# DM1097_MODULE.net
KiCad netlist of a schematic drawn in Altium Designer
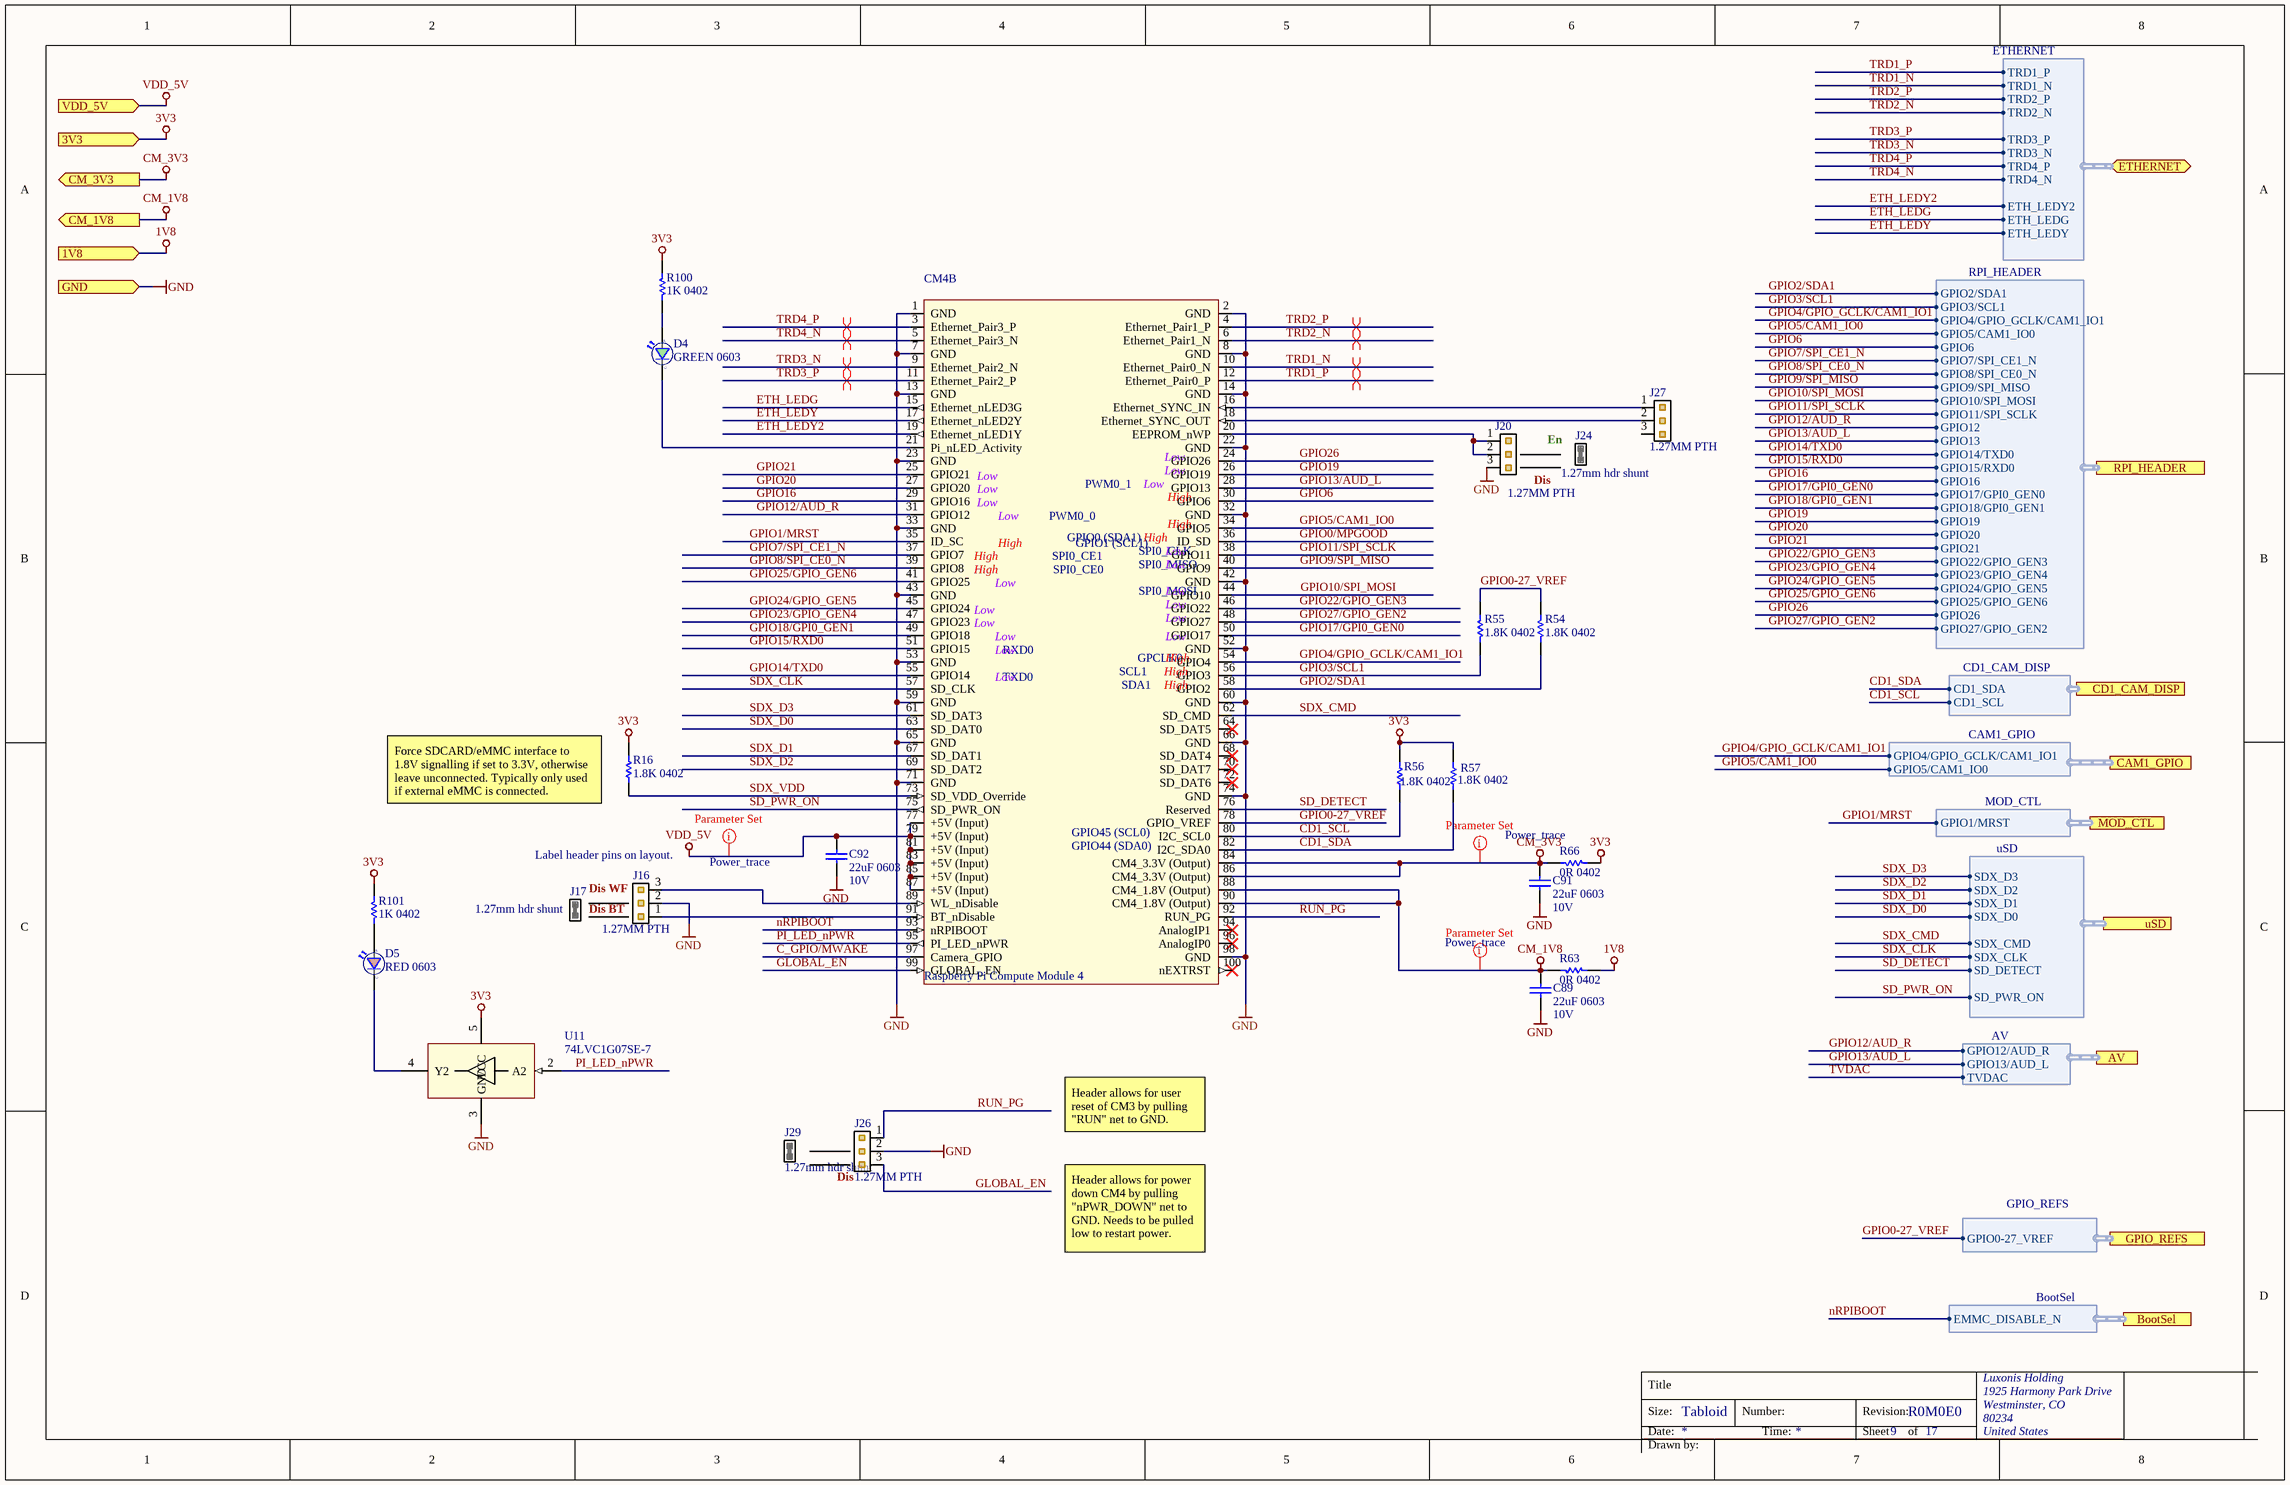
[diagram p0: DM1097_MODULE.SchDoc]

(export (version "E")
  (design (tool "Eeschema 10.0.6"))
  (components
    (comp (ref "C89")
      (value "22uF 0603")
      (footprint "CAP_Altium_Vault_Generic:CAPC0603(1608)100_N")
      (description "CAP CER 22UF 10V X5R 0603 20%")
      (fields (field (name "TOLERANCE") "20%") (field (name "VOLTAGE RATING") "10V"))
      (libsource (lib "LuxonisMaster") (part "GRM188R61A226ME15D"))
    )
    (comp (ref "C91")
      (value "22uF 0603")
      (footprint "CAP_Altium_Vault_Generic:CAPC0603(1608)100_N")
      (description "CAP CER 22UF 10V X5R 0603 20%")
      (fields (field (name "TOLERANCE") "20%") (field (name "VOLTAGE RATING") "10V"))
      (libsource (lib "LuxonisMaster") (part "GRM188R61A226ME15D"))
    )
    (comp (ref "C92")
      (value "22uF 0603")
      (footprint "CAP_Altium_Vault_Generic:CAPC0603(1608)100_N")
      (description "CAP CER 22UF 10V X5R 0603 20%")
      (fields (field (name "TOLERANCE") "20%") (field (name "VOLTAGE RATING") "10V"))
      (libsource (lib "LuxonisMaster") (part "GRM188R61A226ME15D"))
    )
    (comp (ref "CM4")
      (value "Raspberry Pi Compute Module 4")
      (footprint "CM4-DF40HC(3.0)-100DS-0.4v_3mm_1.5mm")
      (description "Raspberry Pi Compute Module 4\r\nTwo receptacle 100-pin connectors")
      (libsource (lib "DM1097_SchLib") (part "CM4"))
    )
    (comp (ref "D4")
      (value "GREEN 0603")
      (footprint "LuxonisMaster:SML_D1xx8W")
      (description "LED GREEN DIFFUSED 0603 SMD Green 572nm LED Indication - Discrete 2.2V 0603 (1608 Metric)")
      (fields (field (name "MANUFACTURER") "Rohm") (field (name "MANUFACTURER PART NUMBER") "SML-D12M8WT86"))
      (libsource (lib "LuxonisMaster") (part "SML-D12M8WT86"))
    )
    (comp (ref "D5")
      (value "RED 0603")
      (footprint "LuxonisMaster:SML_D1xx8W")
      (description "LED RED DIFFUSED 0603 SMD Red 620nm LED Indication - Discrete 2.2V 0603 (1608 Metric)")
      (libsource (lib "LuxonisMaster") (part "SML-D12U8WT86"))
    )
    (comp (ref "J16")
      (value "1.27MM PTH")
      (footprint "LuxonisMaster:GRPB031VWVN-RC")
      (description "CONN HEADER VERT 3POS 1.27MM")
      (libsource (lib "") (part "GRPB031VWVN-RC_2"))
    )
    (comp (ref "J17")
      (value "1.27mm hdr shunt")
      (footprint "LuxonisMaster:M50-1900005")
      (description "CONN SHUNT 1.27MM BLACK")
      (libsource (lib "LuxonisMaster") (part "M50-1900005"))
    )
    (comp (ref "J20")
      (value "1.27MM PTH")
      (footprint "LuxonisMaster:GRPB031VWVN-RC")
      (description "CONN HEADER VERT 3POS 1.27MM")
      (libsource (lib "") (part "GRPB031VWVN-RC_1"))
    )
    (comp (ref "J24")
      (value "1.27mm hdr shunt")
      (footprint "LuxonisMaster:M50-1900005")
      (description "CONN SHUNT 1.27MM BLACK")
      (libsource (lib "") (part "M50-1900005_1"))
    )
    (comp (ref "J26")
      (value "1.27MM PTH")
      (footprint "LuxonisMaster:GRPB031VWVN-RC")
      (description "CONN HEADER VERT 3POS 1.27MM")
      (libsource (lib "LuxonisMaster") (part "GRPB031VWVN-RC"))
    )
    (comp (ref "J27")
      (value "1.27MM PTH")
      (footprint "LuxonisMaster:GRPB031VWVN-RC")
      (description "CONN HEADER VERT 3POS 1.27MM")
      (libsource (lib "") (part "GRPB031VWVN-RC_1"))
    )
    (comp (ref "J29")
      (value "1.27mm hdr shunt")
      (footprint "LuxonisMaster:M50-1900005")
      (description "CONN SHUNT 1.27MM BLACK")
      (libsource (lib "LuxonisMaster") (part "M50-1900005"))
    )
    (comp (ref "R16")
      (value "1.8K 0402")
      (footprint "RES_Altium_Vault_Generic:RESC0402(1005)_N")
      (description "RES SMD 1.8K OHM 1% 1/16W 0402")
      (fields (field (name "TOLERANCE") "1%"))
      (libsource (lib "LuxonisMaster") (part "RC0402FR-071K8L"))
    )
    (comp (ref "R54")
      (value "1.8K 0402")
      (footprint "RES_Altium_Vault_Generic:RESC0402(1005)_N")
      (description "RES SMD 1.8K OHM 1% 1/16W 0402")
      (fields (field (name "TOLERANCE") "1%"))
      (libsource (lib "LuxonisMaster") (part "RC0402FR-071K8L"))
    )
    (comp (ref "R55")
      (value "1.8K 0402")
      (footprint "RES_Altium_Vault_Generic:RESC0402(1005)_N")
      (description "RES SMD 1.8K OHM 1% 1/16W 0402")
      (fields (field (name "TOLERANCE") "1%"))
      (libsource (lib "LuxonisMaster") (part "RC0402FR-071K8L"))
    )
    (comp (ref "R56")
      (value "1.8K 0402")
      (footprint "RES_Altium_Vault_Generic:RESC0402(1005)_N")
      (description "RES SMD 1.8K OHM 1% 1/16W 0402")
      (fields (field (name "TOLERANCE") "1%"))
      (libsource (lib "LuxonisMaster") (part "RC0402FR-071K8L"))
    )
    (comp (ref "R57")
      (value "1.8K 0402")
      (footprint "RES_Altium_Vault_Generic:RESC0402(1005)_N")
      (description "RES SMD 1.8K OHM 1% 1/16W 0402")
      (fields (field (name "TOLERANCE") "1%"))
      (libsource (lib "LuxonisMaster") (part "RC0402FR-071K8L"))
    )
    (comp (ref "R63")
      (value "0R 0402")
      (footprint "RES_Altium_Vault_Generic:RESC0402(1005)_N")
      (description "RES SMD 0 OHM JUMPER 1/16W 0402")
      (fields (field (name "TOLERANCE") "5%"))
      (libsource (lib "LuxonisMaster") (part "CRCW04020000Z0ED"))
    )
    (comp (ref "R66")
      (value "0R 0402")
      (footprint "RES_Altium_Vault_Generic:RESC0402(1005)_N")
      (description "RES SMD 0 OHM JUMPER 1/16W 0402")
      (fields (field (name "TOLERANCE") "5%"))
      (libsource (lib "LuxonisMaster") (part "CRCW04020000Z0ED"))
    )
    (comp (ref "R100")
      (value "1K 0402")
      (footprint "RES_Altium_Vault_Generic:RESC0402(1005)_N")
      (fields (field (name "TOLERANCE") "1%"))
      (libsource (lib "LuxonisMaster") (part "RC0402FR-071KL"))
    )
    (comp (ref "R101")
      (value "1K 0402")
      (footprint "RES_Altium_Vault_Generic:RESC0402(1005)_N")
      (fields (field (name "TOLERANCE") "1%"))
      (libsource (lib "LuxonisMaster") (part "RC0402FR-071KL"))
    )
    (comp (ref "U11")
      (value "74LVC1G07SE-7")
      (footprint "74LVC1G07SE-7")
      (description "SINGLE BUFFER/DRIVER WITH OPEN DRAIN OUTPUT")
      (libsource (lib "DM1097_SchLib") (part "74LVC1G07SE-7"))
    )
  )
  (nets
    (net (code "10") (name "/CD1_SCL") (class "Default")
      (node (ref "CM4") (pin "80") (pinfunction "I2C_SCL0_80") (pintype "passive"))
      (node (ref "R56") (pin "1") (pinfunction "1_1") (pintype "passive"))
    )
    (net (code "11") (name "/CD1_SDA") (class "Default")
      (node (ref "CM4") (pin "82") (pinfunction "I2C_SDA0_82") (pintype "passive"))
      (node (ref "R57") (pin "1") (pinfunction "1_1") (pintype "passive"))
    )
    (net (code "12") (name "/C_GPIO{slash}MWAKE") (class "Default")
      (node (ref "CM4") (pin "97") (pinfunction "Camera_GPIO_97") (pintype "passive"))
    )
    (net (code "13") (name "/ETH_LEDG") (class "Default")
      (node (ref "CM4") (pin "15") (pinfunction "Ethernet_nLED3G_15") (pintype "output"))
    )
    (net (code "14") (name "/ETH_LEDY") (class "Default")
      (node (ref "CM4") (pin "17") (pinfunction "Ethernet_nLED2Y_17") (pintype "output"))
    )
    (net (code "15") (name "/ETH_LEDY2") (class "Default")
      (node (ref "CM4") (pin "19") (pinfunction "Ethernet_nLED1Y_19") (pintype "output"))
    )
    (net (code "16") (name "/GLOBAL_EN") (class "Default")
      (node (ref "CM4") (pin "99") (pinfunction "GLOBAL_EN_99") (pintype "input"))
      (node (ref "J26") (pin "3") (pinfunction "3_3") (pintype "passive"))
    )
    (net (code "17") (name "/GPIO0-27_VREF") (class "Default")
      (node (ref "CM4") (pin "78") (pinfunction "GPIO_VREF_78") (pintype "power_in"))
      (node (ref "R54") (pin "2") (pinfunction "2_2") (pintype "passive"))
      (node (ref "R55") (pin "2") (pinfunction "2_2") (pintype "passive"))
    )
    (net (code "18") (name "/GPIO0{slash}MPGOOD") (class "Default")
      (node (ref "CM4") (pin "36") (pinfunction "ID_SD_36") (pintype "passive"))
    )
    (net (code "19") (name "/GPIO1{slash}MRST") (class "Default")
      (node (ref "CM4") (pin "35") (pinfunction "ID_SC_35") (pintype "passive"))
    )
    (net (code "20") (name "/GPIO2{slash}SDA1") (class "Default")
      (node (ref "CM4") (pin "58") (pinfunction "GPIO2_58") (pintype "passive"))
      (node (ref "R54") (pin "1") (pinfunction "1_1") (pintype "passive"))
    )
    (net (code "21") (name "/GPIO3{slash}SCL1") (class "Default")
      (node (ref "CM4") (pin "56") (pinfunction "GPIO3_56") (pintype "passive"))
      (node (ref "R55") (pin "1") (pinfunction "1_1") (pintype "passive"))
    )
    (net (code "22") (name "/GPIO4{slash}GPIO_GCLK{slash}CAM1_IO1") (class "Default")
      (node (ref "CM4") (pin "54") (pinfunction "GPIO4_54") (pintype "passive"))
    )
    (net (code "23") (name "/GPIO5{slash}CAM1_IO0") (class "Default")
      (node (ref "CM4") (pin "34") (pinfunction "GPIO5_34") (pintype "passive"))
    )
    (net (code "24") (name "/GPIO6") (class "Default")
      (node (ref "CM4") (pin "30") (pinfunction "GPIO6_30") (pintype "passive"))
    )
    (net (code "25") (name "/GPIO7{slash}SPI_CE1_N") (class "Default")
      (node (ref "CM4") (pin "37") (pinfunction "GPIO7_37") (pintype "passive"))
    )
    (net (code "26") (name "/GPIO8{slash}SPI_CE0_N") (class "Default")
      (node (ref "CM4") (pin "39") (pinfunction "GPIO8_39") (pintype "passive"))
    )
    (net (code "27") (name "/GPIO9{slash}SPI_MISO") (class "Default")
      (node (ref "CM4") (pin "40") (pinfunction "GPIO9_40") (pintype "passive"))
    )
    (net (code "28") (name "/GPIO10{slash}SPI_MOSI") (class "Default")
      (node (ref "CM4") (pin "44") (pinfunction "GPIO10_44") (pintype "passive"))
    )
    (net (code "29") (name "/GPIO11{slash}SPI_SCLK") (class "Default")
      (node (ref "CM4") (pin "38") (pinfunction "GPIO11_38") (pintype "passive"))
    )
    (net (code "30") (name "/GPIO12{slash}AUD_R") (class "Default")
      (node (ref "CM4") (pin "31") (pinfunction "GPIO12_31") (pintype "passive"))
    )
    (net (code "31") (name "/GPIO13{slash}AUD_L") (class "Default")
      (node (ref "CM4") (pin "28") (pinfunction "GPIO13_28") (pintype "passive"))
    )
    (net (code "32") (name "/GPIO14{slash}TXD0") (class "Default")
      (node (ref "CM4") (pin "55") (pinfunction "GPIO14_55") (pintype "passive"))
    )
    (net (code "33") (name "/GPIO15{slash}RXD0") (class "Default")
      (node (ref "CM4") (pin "51") (pinfunction "GPIO15_51") (pintype "passive"))
    )
    (net (code "34") (name "/GPIO16") (class "Default")
      (node (ref "CM4") (pin "29") (pinfunction "GPIO16_29") (pintype "passive"))
    )
    (net (code "35") (name "/GPIO17{slash}GPI0_GEN0") (class "Default")
      (node (ref "CM4") (pin "50") (pinfunction "GPIO17_50") (pintype "passive"))
    )
    (net (code "36") (name "/GPIO18{slash}GPI0_GEN1") (class "Default")
      (node (ref "CM4") (pin "49") (pinfunction "GPIO18_49") (pintype "passive"))
    )
    (net (code "37") (name "/GPIO19") (class "Default")
      (node (ref "CM4") (pin "26") (pinfunction "GPIO19_26") (pintype "passive"))
    )
    (net (code "38") (name "/GPIO20") (class "Default")
      (node (ref "CM4") (pin "27") (pinfunction "GPIO20_27") (pintype "passive"))
    )
    (net (code "39") (name "/GPIO21") (class "Default")
      (node (ref "CM4") (pin "25") (pinfunction "GPIO21_25") (pintype "passive"))
    )
    (net (code "40") (name "/GPIO22{slash}GPIO_GEN3") (class "Default")
      (node (ref "CM4") (pin "46") (pinfunction "GPIO22_46") (pintype "passive"))
    )
    (net (code "41") (name "/GPIO23{slash}GPIO_GEN4") (class "Default")
      (node (ref "CM4") (pin "47") (pinfunction "GPIO23_47") (pintype "passive"))
    )
    (net (code "42") (name "/GPIO24{slash}GPIO_GEN5") (class "Default")
      (node (ref "CM4") (pin "45") (pinfunction "GPIO24_45") (pintype "passive"))
    )
    (net (code "43") (name "/GPIO25{slash}GPIO_GEN6") (class "Default")
      (node (ref "CM4") (pin "41") (pinfunction "GPIO25_41") (pintype "passive"))
    )
    (net (code "44") (name "/GPIO26") (class "Default")
      (node (ref "CM4") (pin "24") (pinfunction "GPIO26_24") (pintype "passive"))
    )
    (net (code "45") (name "/GPIO27{slash}GPIO_GEN2") (class "Default")
      (node (ref "CM4") (pin "48") (pinfunction "GPIO27_48") (pintype "passive"))
    )
    (net (code "46") (name "/PI_LED_nPWR") (class "Default")
      (node (ref "CM4") (pin "95") (pinfunction "PI_LED_nPWR_95") (pintype "output"))
      (node (ref "U11") (pin "2") (pinfunction "A2_2") (pintype "input"))
    )
    (net (code "47") (name "/RUN_PG") (class "Default")
      (node (ref "CM4") (pin "92") (pinfunction "RUN_PG_92") (pintype "passive"))
      (node (ref "J26") (pin "1") (pinfunction "1_1") (pintype "passive"))
    )
    (net (code "48") (name "/SDX_CLK") (class "Default")
      (node (ref "CM4") (pin "57") (pinfunction "SD_CLK_57") (pintype "passive"))
    )
    (net (code "49") (name "/SDX_CMD") (class "Default")
      (node (ref "CM4") (pin "62") (pinfunction "SD_CMD_62") (pintype "passive"))
    )
    (net (code "50") (name "/SDX_D0") (class "Default")
      (node (ref "CM4") (pin "63") (pinfunction "SD_DAT0_63") (pintype "passive"))
    )
    (net (code "51") (name "/SDX_D1") (class "Default")
      (node (ref "CM4") (pin "67") (pinfunction "SD_DAT1_67") (pintype "passive"))
    )
    (net (code "52") (name "/SDX_D2") (class "Default")
      (node (ref "CM4") (pin "69") (pinfunction "SD_DAT2_69") (pintype "passive"))
    )
    (net (code "53") (name "/SDX_D3") (class "Default")
      (node (ref "CM4") (pin "61") (pinfunction "SD_DAT3_61") (pintype "passive"))
    )
    (net (code "54") (name "/SDX_VDD") (class "Default")
      (node (ref "CM4") (pin "73") (pinfunction "SD_VDD_Override_73") (pintype "input"))
      (node (ref "R16") (pin "1") (pinfunction "1_1") (pintype "passive"))
    )
    (net (code "55") (name "/SD_DETECT") (class "Default")
      (node (ref "CM4") (pin "76") (pinfunction "Reserved_76") (pintype "passive"))
    )
    (net (code "56") (name "/SD_PWR_ON") (class "Default")
      (node (ref "CM4") (pin "75") (pinfunction "SD_PWR_ON_75") (pintype "output"))
    )
    (net (code "57") (name "/TRD1_N") (class "Default")
      (node (ref "CM4") (pin "10") (pinfunction "Ethernet_Pair0_N_10") (pintype "passive"))
    )
    (net (code "58") (name "/TRD1_P") (class "Default")
      (node (ref "CM4") (pin "12") (pinfunction "Ethernet_Pair0_P_12") (pintype "passive"))
    )
    (net (code "59") (name "/TRD2_N") (class "Default")
      (node (ref "CM4") (pin "6") (pinfunction "Ethernet_Pair1_N_6") (pintype "passive"))
    )
    (net (code "60") (name "/TRD2_P") (class "Default")
      (node (ref "CM4") (pin "4") (pinfunction "Ethernet_Pair1_P_4") (pintype "passive"))
    )
    (net (code "61") (name "/TRD3_N") (class "Default")
      (node (ref "CM4") (pin "9") (pinfunction "Ethernet_Pair2_N_9") (pintype "passive"))
    )
    (net (code "62") (name "/TRD3_P") (class "Default")
      (node (ref "CM4") (pin "11") (pinfunction "Ethernet_Pair2_P_11") (pintype "passive"))
    )
    (net (code "63") (name "/TRD4_N") (class "Default")
      (node (ref "CM4") (pin "5") (pinfunction "Ethernet_Pair3_N_5") (pintype "passive"))
    )
    (net (code "64") (name "/TRD4_P") (class "Default")
      (node (ref "CM4") (pin "3") (pinfunction "Ethernet_Pair3_P_3") (pintype "passive"))
    )
    (net (code "66") (name "/nRPIBOOT") (class "Default")
      (node (ref "CM4") (pin "93") (pinfunction "nRPIBOOT_93") (pintype "input"))
    )
    (net (code "76") (name "1V8") (class "Default")
      (node (ref "R63") (pin "1") (pinfunction "1_1") (pintype "passive"))
    )
    (net (code "77") (name "3V3") (class "Default")
      (node (ref "R100") (pin "2") (pinfunction "2_2") (pintype "passive"))
      (node (ref "R101") (pin "2") (pinfunction "2_2") (pintype "passive"))
      (node (ref "R16") (pin "2") (pinfunction "2_2") (pintype "passive"))
      (node (ref "R56") (pin "2") (pinfunction "2_2") (pintype "passive"))
      (node (ref "R57") (pin "2") (pinfunction "2_2") (pintype "passive"))
      (node (ref "R66") (pin "1") (pinfunction "1_1") (pintype "passive"))
      (node (ref "U11") (pin "5") (pinfunction "VCC_5") (pintype "power_in"))
    )
    (net (code "78") (name "CM_1V8") (class "Default")
      (node (ref "C89") (pin "1") (pinfunction "1_1") (pintype "passive"))
      (node (ref "CM4") (pin "88") (pinfunction "CM4_1.8V_(Output)_88") (pintype "power_in"))
      (node (ref "CM4") (pin "90") (pinfunction "CM4_1.8V_(Output)_90") (pintype "power_in"))
      (node (ref "R63") (pin "2") (pinfunction "2_2") (pintype "passive"))
    )
    (net (code "79") (name "CM_3V3") (class "Default")
      (node (ref "C91") (pin "1") (pinfunction "1_1") (pintype "passive"))
      (node (ref "CM4") (pin "84") (pinfunction "CM4_3.3V_(Output)_84") (pintype "power_in"))
      (node (ref "CM4") (pin "86") (pinfunction "CM4_3.3V_(Output)_86") (pintype "power_in"))
      (node (ref "R66") (pin "2") (pinfunction "2_2") (pintype "passive"))
    )
    (net (code "80") (name "GND") (class "Default")
      (node (ref "C89") (pin "2") (pinfunction "2_2") (pintype "passive"))
      (node (ref "C91") (pin "2") (pinfunction "2_2") (pintype "passive"))
      (node (ref "C92") (pin "2") (pinfunction "2_2") (pintype "passive"))
      (node (ref "CM4") (pin "1") (pinfunction "GND_1") (pintype "power_in"))
      (node (ref "CM4") (pin "13") (pinfunction "GND_13") (pintype "power_in"))
      (node (ref "CM4") (pin "14") (pinfunction "GND_14") (pintype "power_in"))
      (node (ref "CM4") (pin "2") (pinfunction "GND_2") (pintype "power_in"))
      (node (ref "CM4") (pin "22") (pinfunction "GND_22") (pintype "power_in"))
      (node (ref "CM4") (pin "23") (pinfunction "GND_23") (pintype "power_in"))
      (node (ref "CM4") (pin "32") (pinfunction "GND_32") (pintype "power_in"))
      (node (ref "CM4") (pin "33") (pinfunction "GND_33") (pintype "power_in"))
      (node (ref "CM4") (pin "42") (pinfunction "GND_42") (pintype "power_in"))
      (node (ref "CM4") (pin "43") (pinfunction "GND_43") (pintype "power_in"))
      (node (ref "CM4") (pin "52") (pinfunction "GND_52") (pintype "power_in"))
      (node (ref "CM4") (pin "53") (pinfunction "GND_53") (pintype "power_in"))
      (node (ref "CM4") (pin "59") (pinfunction "GND_59") (pintype "power_in"))
      (node (ref "CM4") (pin "60") (pinfunction "GND_60") (pintype "power_in"))
      (node (ref "CM4") (pin "65") (pinfunction "GND_65") (pintype "power_in"))
      (node (ref "CM4") (pin "66") (pinfunction "GND_66") (pintype "power_in"))
      (node (ref "CM4") (pin "7") (pinfunction "GND_7") (pintype "power_in"))
      (node (ref "CM4") (pin "71") (pinfunction "GND_71") (pintype "power_in"))
      (node (ref "CM4") (pin "74") (pinfunction "GND_74") (pintype "power_in"))
      (node (ref "CM4") (pin "8") (pinfunction "GND_8") (pintype "power_in"))
      (node (ref "CM4") (pin "98") (pinfunction "GND_98") (pintype "power_in"))
      (node (ref "J16") (pin "2") (pinfunction "2_2") (pintype "passive"))
      (node (ref "J20") (pin "3") (pinfunction "3_3") (pintype "passive"))
      (node (ref "J26") (pin "2") (pinfunction "2_2") (pintype "passive"))
      (node (ref "U11") (pin "3") (pinfunction "GND_3") (pintype "power_in"))
    )
    (net (code "81") (name "Net-(CM4B-BT_nDisable)") (class "Default")
      (node (ref "CM4") (pin "91") (pinfunction "BT_nDisable_91") (pintype "input"))
      (node (ref "J16") (pin "1") (pinfunction "1_1") (pintype "passive"))
    )
    (net (code "82") (name "Net-(CM4B-EEPROM_nWP)") (class "Default")
      (node (ref "CM4") (pin "20") (pinfunction "EEPROM_nWP_20") (pintype "passive"))
      (node (ref "J20") (pin "1") (pinfunction "1_1") (pintype "passive"))
      (node (ref "J20") (pin "2") (pinfunction "2_2") (pintype "passive"))
    )
    (net (code "83") (name "Net-(CM4B-Ethernet_SYNC_IN)") (class "Default")
      (node (ref "CM4") (pin "16") (pinfunction "Ethernet_SYNC_IN_16") (pintype "input"))
      (node (ref "J27") (pin "1") (pinfunction "1_1") (pintype "passive"))
    )
    (net (code "84") (name "Net-(CM4B-Ethernet_SYNC_OUT)") (class "Default")
      (node (ref "CM4") (pin "18") (pinfunction "Ethernet_SYNC_OUT_18") (pintype "input"))
      (node (ref "J27") (pin "2") (pinfunction "2_2") (pintype "passive"))
    )
    (net (code "85") (name "Net-(CM4B-Pi_nLED_Activity)") (class "Default")
      (node (ref "CM4") (pin "21") (pinfunction "Pi_nLED_Activity_21") (pintype "open_collector"))
      (node (ref "D4") (pin "1") (pinfunction "C_1") (pintype "passive"))
    )
    (net (code "86") (name "Net-(CM4B-WL_nDisable)") (class "Default")
      (node (ref "CM4") (pin "89") (pinfunction "WL_nDisable_89") (pintype "input"))
      (node (ref "J16") (pin "3") (pinfunction "3_3") (pintype "passive"))
    )
    (net (code "87") (name "Net-(D4-A)") (class "Default")
      (node (ref "D4") (pin "2") (pinfunction "A_2") (pintype "passive"))
      (node (ref "R100") (pin "1") (pinfunction "1_1") (pintype "passive"))
    )
    (net (code "88") (name "Net-(D5-A)") (class "Default")
      (node (ref "D5") (pin "2") (pinfunction "A_2") (pintype "passive"))
      (node (ref "R101") (pin "1") (pinfunction "1_1") (pintype "passive"))
    )
    (net (code "89") (name "Net-(D5-C)") (class "Default")
      (node (ref "D5") (pin "1") (pinfunction "C_1") (pintype "passive"))
      (node (ref "U11") (pin "4") (pinfunction "Y2_4") (pintype "open_collector"))
    )
    (net (code "90") (name "VDD_5V") (class "Default")
      (node (ref "C92") (pin "1") (pinfunction "1_1") (pintype "passive"))
      (node (ref "CM4") (pin "77") (pinfunction "+5V_(Input)_77") (pintype "power_in"))
      (node (ref "CM4") (pin "79") (pinfunction "+5V_(Input)_79") (pintype "power_in"))
      (node (ref "CM4") (pin "81") (pinfunction "+5V_(Input)_81") (pintype "power_in"))
      (node (ref "CM4") (pin "83") (pinfunction "+5V_(Input)_83") (pintype "power_in"))
      (node (ref "CM4") (pin "85") (pinfunction "+5V_(Input)_85") (pintype "power_in"))
      (node (ref "CM4") (pin "87") (pinfunction "+5V_(Input)_87") (pintype "power_in"))
    )
    (net (code "91") (name "unconnected-(CM4B-AnalogIP0-Pad96)") (class "Default")
      (node (ref "CM4") (pin "96") (pinfunction "AnalogIP0_96") (pintype "passive+no_connect"))
    )
    (net (code "92") (name "unconnected-(CM4B-AnalogIP1-Pad94)") (class "Default")
      (node (ref "CM4") (pin "94") (pinfunction "AnalogIP1_94") (pintype "passive+no_connect"))
    )
    (net (code "93") (name "unconnected-(CM4B-SD_DAT4-Pad68)") (class "Default")
      (node (ref "CM4") (pin "68") (pinfunction "SD_DAT4_68") (pintype "passive+no_connect"))
    )
    (net (code "94") (name "unconnected-(CM4B-SD_DAT5-Pad64)") (class "Default")
      (node (ref "CM4") (pin "64") (pinfunction "SD_DAT5_64") (pintype "passive+no_connect"))
    )
    (net (code "95") (name "unconnected-(CM4B-SD_DAT6-Pad72)") (class "Default")
      (node (ref "CM4") (pin "72") (pinfunction "SD_DAT6_72") (pintype "passive+no_connect"))
    )
    (net (code "96") (name "unconnected-(CM4B-SD_DAT7-Pad70)") (class "Default")
      (node (ref "CM4") (pin "70") (pinfunction "SD_DAT7_70") (pintype "passive+no_connect"))
    )
    (net (code "97") (name "unconnected-(CM4B-nEXTRST-Pad100)") (class "Default")
      (node (ref "CM4") (pin "100") (pinfunction "nEXTRST_100") (pintype "output+no_connect"))
    )
    (net (code "98") (name "unconnected-(J27-Pad3)") (class "Default")
      (node (ref "J27") (pin "3") (pinfunction "3_3") (pintype "passive"))
    )
  )
)
